# Buzzer.net
KiCad netlist of a schematic drawn in Altium Designer
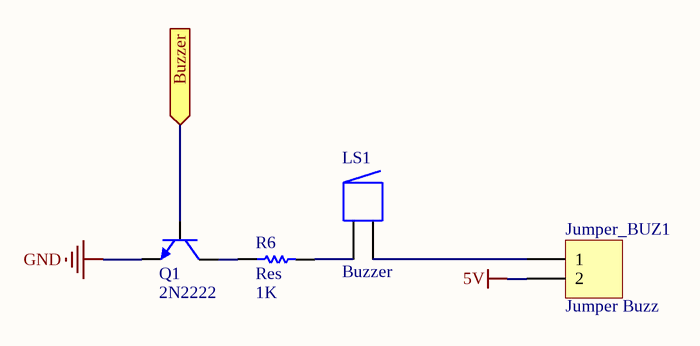
[diagram p0: Buzzer.SchDoc]

(export (version "E")
  (design (tool "Eeschema 10.0.6"))
  (components
    (comp (ref "Jumper_BUZ1")
      (value "Jumper Buzz")
      (footprint "HDR1X2")
      (description "Header, 2-Pin")
      (fields (field (name "PUBLISHER") "Altium Limited"))
      (libsource (lib "Miscellaneous Connectors") (part "Header 2"))
    )
    (comp (ref "LS1")
      (value "Buzzer")
      (footprint "BUZZER")
      (description "Magnetic Transducer Buzzer")
      (fields (field (name "PUBLISHER") "Altium Limited"))
      (libsource (lib "KN2CLib") (part "Buzzer"))
    )
    (comp (ref "Q1")
      (value "2N2222")
      (footprint "SOT-23")
      (description "NPN Bipolar Transistor")
      (fields (field (name "PUBLISHER") "Altium Limited"))
      (libsource (lib "KN2CLib") (part "2N2222"))
    )
    (comp (ref "R6")
      (value "Res")
      (footprint "2012[0805]")
      (description "Semiconductor Resistor")
      (fields (field (name "ALTIUM_VALUE") "1K") (field (name "PUBLISHER") "Altium Limited"))
      (libsource (lib "KN2CLib") (part "Res"))
    )
  )
  (nets
    (net (code "1") (name "/Buzzer") (class "Default")
      (node (ref "Q1") (pin "2") (pinfunction "B_2") (pintype "passive"))
    )
    (net (code "2") (name "5V") (class "Default")
      (node (ref "Jumper_BUZ1") (pin "2") (pinfunction "2_2") (pintype "passive"))
    )
    (net (code "3") (name "GND") (class "Default")
      (node (ref "Q1") (pin "3") (pinfunction "E_3") (pintype "passive"))
    )
    (net (code "4") (name "Net-(Jumper_BUZ1-Pad1)") (class "Default")
      (node (ref "Jumper_BUZ1") (pin "1") (pinfunction "1_1") (pintype "passive"))
      (node (ref "LS1") (pin "2") (pinfunction "2_2") (pintype "passive"))
    )
    (net (code "5") (name "Net-(LS1-Pad1)") (class "Default")
      (node (ref "LS1") (pin "1") (pinfunction "1_1") (pintype "passive"))
      (node (ref "R6") (pin "2") (pinfunction "2_2") (pintype "passive"))
    )
    (net (code "6") (name "Net-(Q1-C)") (class "Default")
      (node (ref "Q1") (pin "1") (pinfunction "C_1") (pintype "passive"))
      (node (ref "R6") (pin "1") (pinfunction "1_1") (pintype "passive"))
    )
  )
)
